# TailLightPrototype.net
KiCad netlist of a schematic drawn in Altium Designer
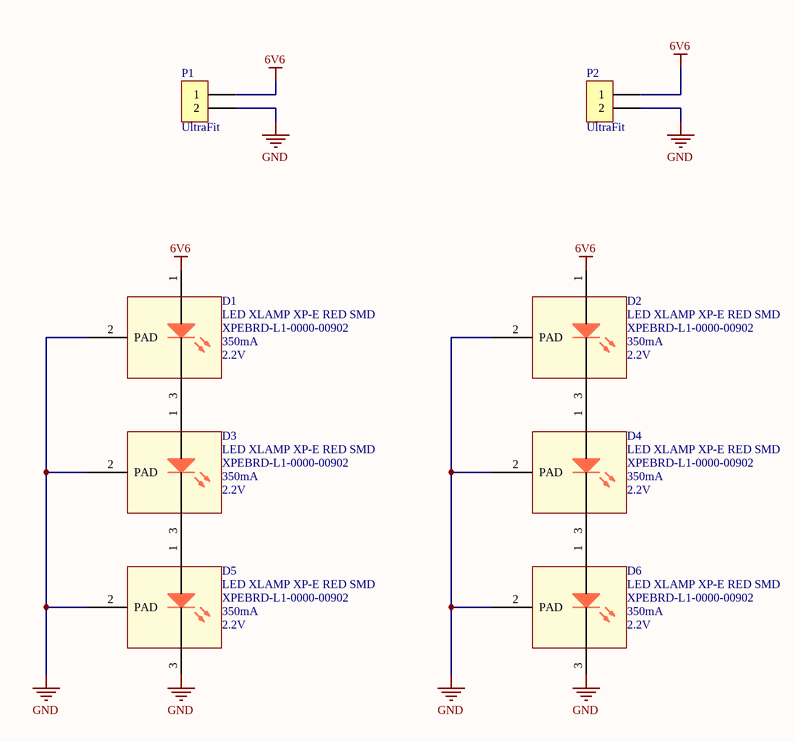
[diagram p0: TailLightPrototype.SchDoc]

(export (version "E")
  (design (tool "Eeschema 10.0.6"))
  (components
    (comp (ref "D1")
      (value "LED XLAMP XP-E RED SMD")
      (footprint "LED CREE XP-E2 1414 2-SMD")
      (description "LED Lighting Color XLamp® XP-E2 Red 623nm (620nm ~ 625nm) 1414 (3535 Metric)")
      (fields
        (field (name "MANUFACTURER") "Cree")
        (field (name "MANUFACTURER PART NUMBER") "XPEBRD-L1-0000-00902")
        (field (name "TEST CURRENT") "350mA")
        (field (name "FORWARD VOLTAGE") "2.2V")
      )
      (libsource (lib "Schematic Diagrams") (part "LED XLAMP XP-E RED SMD"))
    )
    (comp (ref "D2")
      (value "LED XLAMP XP-E RED SMD")
      (footprint "LED CREE XP-E2 1414 2-SMD")
      (description "LED Lighting Color XLamp® XP-E2 Red 623nm (620nm ~ 625nm) 1414 (3535 Metric)")
      (fields
        (field (name "MANUFACTURER") "Cree")
        (field (name "MANUFACTURER PART NUMBER") "XPEBRD-L1-0000-00902")
        (field (name "TEST CURRENT") "350mA")
        (field (name "FORWARD VOLTAGE") "2.2V")
      )
      (libsource (lib "Schematic Diagrams") (part "LED XLAMP XP-E RED SMD"))
    )
    (comp (ref "D3")
      (value "LED XLAMP XP-E RED SMD")
      (footprint "LED CREE XP-E2 1414 2-SMD")
      (description "LED Lighting Color XLamp® XP-E2 Red 623nm (620nm ~ 625nm) 1414 (3535 Metric)")
      (fields
        (field (name "MANUFACTURER") "Cree")
        (field (name "MANUFACTURER PART NUMBER") "XPEBRD-L1-0000-00902")
        (field (name "TEST CURRENT") "350mA")
        (field (name "FORWARD VOLTAGE") "2.2V")
      )
      (libsource (lib "Schematic Diagrams") (part "LED XLAMP XP-E RED SMD"))
    )
    (comp (ref "D4")
      (value "LED XLAMP XP-E RED SMD")
      (footprint "LED CREE XP-E2 1414 2-SMD")
      (description "LED Lighting Color XLamp® XP-E2 Red 623nm (620nm ~ 625nm) 1414 (3535 Metric)")
      (fields
        (field (name "MANUFACTURER") "Cree")
        (field (name "MANUFACTURER PART NUMBER") "XPEBRD-L1-0000-00902")
        (field (name "TEST CURRENT") "350mA")
        (field (name "FORWARD VOLTAGE") "2.2V")
      )
      (libsource (lib "Schematic Diagrams") (part "LED XLAMP XP-E RED SMD"))
    )
    (comp (ref "D5")
      (value "LED XLAMP XP-E RED SMD")
      (footprint "LED CREE XP-E2 1414 2-SMD")
      (description "LED Lighting Color XLamp® XP-E2 Red 623nm (620nm ~ 625nm) 1414 (3535 Metric)")
      (fields
        (field (name "MANUFACTURER") "Cree")
        (field (name "MANUFACTURER PART NUMBER") "XPEBRD-L1-0000-00902")
        (field (name "TEST CURRENT") "350mA")
        (field (name "FORWARD VOLTAGE") "2.2V")
      )
      (libsource (lib "Schematic Diagrams") (part "LED XLAMP XP-E RED SMD"))
    )
    (comp (ref "D6")
      (value "LED XLAMP XP-E RED SMD")
      (footprint "LED CREE XP-E2 1414 2-SMD")
      (description "LED Lighting Color XLamp® XP-E2 Red 623nm (620nm ~ 625nm) 1414 (3535 Metric)")
      (fields
        (field (name "MANUFACTURER") "Cree")
        (field (name "MANUFACTURER PART NUMBER") "XPEBRD-L1-0000-00902")
        (field (name "TEST CURRENT") "350mA")
        (field (name "FORWARD VOLTAGE") "2.2V")
      )
      (libsource (lib "Schematic Diagrams") (part "LED XLAMP XP-E RED SMD"))
    )
    (comp (ref "P1")
      (value "CONN 2POS ULTRA-FIT 0.138\"")
      (footprint "CONN, 2POS ULTRA-FIT")
      (description "2 Positions Header, Shrouded Connector 0.138\" (3.50mm) Through Hole Gold")
      (fields (field (name "VOLTAGE") "400V") (field (name "SERIES") "UltraFit"))
      (libsource (lib "Schematic Diagrams") (part "CONN 2POS ULTRA-FIT 0.138{dblquote}"))
    )
    (comp (ref "P2")
      (value "CONN 2POS ULTRA-FIT 0.138\"")
      (footprint "CONN, 2POS ULTRA-FIT")
      (description "2 Positions Header, Shrouded Connector 0.138\" (3.50mm) Through Hole Gold")
      (fields (field (name "VOLTAGE") "400V") (field (name "SERIES") "UltraFit"))
      (libsource (lib "Schematic Diagrams") (part "CONN 2POS ULTRA-FIT 0.138{dblquote}"))
    )
  )
  (nets
    (net (code "1") (name "6V6") (class "Default")
      (node (ref "D1") (pin "1") (pinfunction "A_1") (pintype "passive"))
      (node (ref "D2") (pin "1") (pinfunction "A_1") (pintype "passive"))
      (node (ref "P1") (pin "1") (pinfunction "1_1") (pintype "passive"))
      (node (ref "P2") (pin "1") (pinfunction "1_1") (pintype "passive"))
    )
    (net (code "2") (name "GND") (class "Default")
      (node (ref "D1") (pin "2") (pinfunction "PAD_2") (pintype "passive"))
      (node (ref "D2") (pin "2") (pinfunction "PAD_2") (pintype "passive"))
      (node (ref "D3") (pin "2") (pinfunction "PAD_2") (pintype "passive"))
      (node (ref "D4") (pin "2") (pinfunction "PAD_2") (pintype "passive"))
      (node (ref "D5") (pin "2") (pinfunction "PAD_2") (pintype "passive"))
      (node (ref "D5") (pin "3") (pinfunction "K_3") (pintype "passive"))
      (node (ref "D6") (pin "2") (pinfunction "PAD_2") (pintype "passive"))
      (node (ref "D6") (pin "3") (pinfunction "K_3") (pintype "passive"))
      (node (ref "P1") (pin "2") (pinfunction "2_2") (pintype "passive"))
      (node (ref "P2") (pin "2") (pinfunction "2_2") (pintype "passive"))
    )
    (net (code "3") (name "Net-(D1-K)") (class "Default")
      (node (ref "D1") (pin "3") (pinfunction "K_3") (pintype "passive"))
      (node (ref "D3") (pin "1") (pinfunction "A_1") (pintype "passive"))
    )
    (net (code "4") (name "Net-(D2-K)") (class "Default")
      (node (ref "D2") (pin "3") (pinfunction "K_3") (pintype "passive"))
      (node (ref "D4") (pin "1") (pinfunction "A_1") (pintype "passive"))
    )
    (net (code "5") (name "Net-(D3-K)") (class "Default")
      (node (ref "D3") (pin "3") (pinfunction "K_3") (pintype "passive"))
      (node (ref "D5") (pin "1") (pinfunction "A_1") (pintype "passive"))
    )
    (net (code "6") (name "Net-(D4-K)") (class "Default")
      (node (ref "D4") (pin "3") (pinfunction "K_3") (pintype "passive"))
      (node (ref "D6") (pin "1") (pinfunction "A_1") (pintype "passive"))
    )
  )
)
